# TS-4900_Headers.net
KiCad netlist of a schematic drawn in Altium Designer
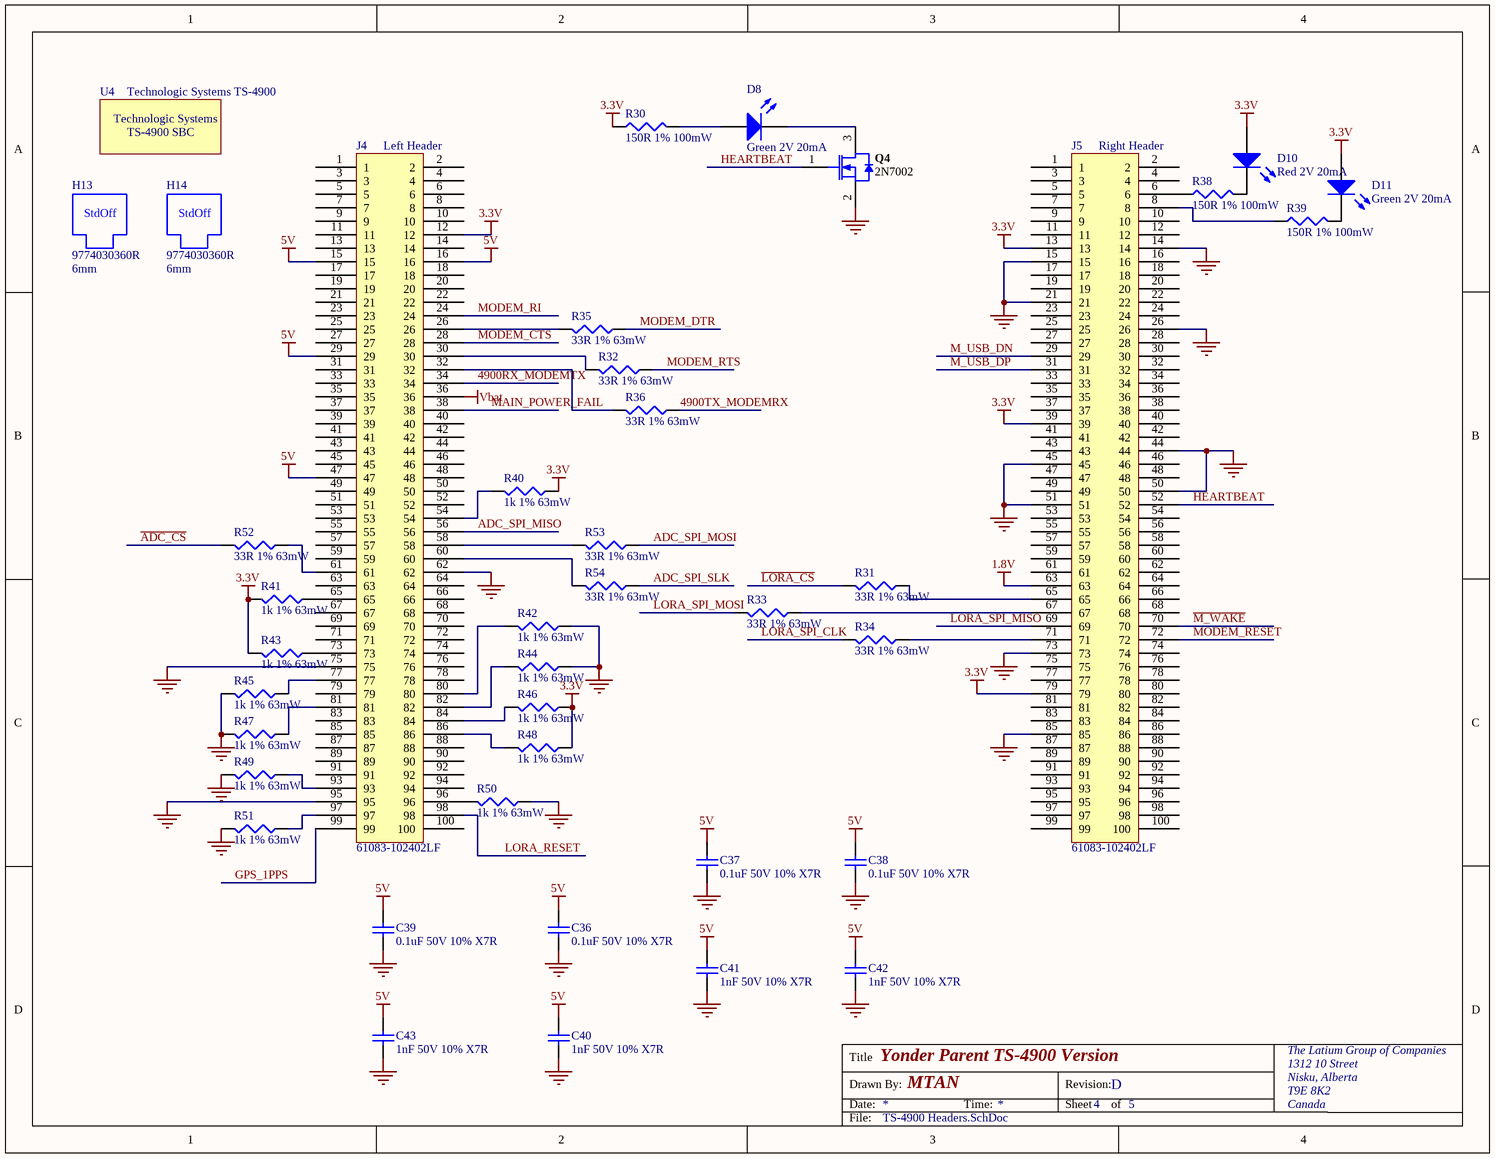
[diagram p0: TS-4900 Headers.SchDoc]

(export (version "E")
  (design (tool "Eeschema 10.0.6"))
  (components
    (comp (ref "C36")
      (value "0.1uF 50V 10% X7R")
      (footprint "CAPC1005L")
      (description "Capacitor")
      (libsource (lib "Miscellaneous Devices") (part "Cap"))
    )
    (comp (ref "C37")
      (value "0.1uF 50V 10% X7R")
      (footprint "CAPC1005L")
      (description "Capacitor")
      (libsource (lib "Miscellaneous Devices") (part "Cap"))
    )
    (comp (ref "C38")
      (value "0.1uF 50V 10% X7R")
      (footprint "CAPC1005L")
      (description "Capacitor")
      (libsource (lib "Miscellaneous Devices") (part "Cap"))
    )
    (comp (ref "C39")
      (value "0.1uF 50V 10% X7R")
      (footprint "CAPC1005L")
      (description "Capacitor")
      (libsource (lib "Miscellaneous Devices") (part "Cap"))
    )
    (comp (ref "C40")
      (value "1nF 50V 10% X7R")
      (footprint "CAPC1005L")
      (description "Capacitor")
      (libsource (lib "Miscellaneous Devices") (part "Cap"))
    )
    (comp (ref "C41")
      (value "1nF 50V 10% X7R")
      (footprint "CAPC1005L")
      (description "Capacitor")
      (libsource (lib "Miscellaneous Devices") (part "Cap"))
    )
    (comp (ref "C42")
      (value "1nF 50V 10% X7R")
      (footprint "CAPC1005L")
      (description "Capacitor")
      (libsource (lib "Miscellaneous Devices") (part "Cap"))
    )
    (comp (ref "C43")
      (value "1nF 50V 10% X7R")
      (footprint "CAPC1005L")
      (description "Capacitor")
      (libsource (lib "Miscellaneous Devices") (part "Cap"))
    )
    (comp (ref "D8")
      (value "Green 2V 20mA")
      (footprint "CD1608-0603")
      (description "LED GREEN CLEAR 0603 SMD")
      (fields
        (field (name "MANUFACTURER") "Wurth Electronics Inc")
        (field (name "MANUFACTURER PART NUMBER") "150060VS75000")
      )
      (libsource (lib "Miscellaneous Devices") (part "LED2"))
    )
    (comp (ref "D10")
      (value "Red 2V 20mA")
      (footprint "CD1608-0603")
      (description "LED RED CLEAR 0603 SMD")
      (fields
        (field (name "MANUFACTURER") "Wurth Electronics Inc")
        (field (name "MANUFACTURER PART NUMBER") "150060RS75000")
      )
      (libsource (lib "Miscellaneous Devices") (part "LED2"))
    )
    (comp (ref "D11")
      (value "Green 2V 20mA")
      (footprint "CD1608-0603")
      (description "LED GREEN CLEAR 0603 SMD")
      (fields
        (field (name "MANUFACTURER") "Wurth Electronics Inc")
        (field (name "MANUFACTURER PART NUMBER") "150060VS75000")
      )
      (libsource (lib "Miscellaneous Devices") (part "LED2"))
    )
    (comp (ref "H13")
      (value "9774030360R")
      (footprint "Wurth 9774060360R")
      (description "ROUND STANDOFF M3X0.5 STEEL 6MM")
      (fields
        (field (name "MANUFACTURER") "Wurth Electronics Inc")
        (field (name "MANUFACTURER PART NUMBER") "9774060360R")
        (field (name "HEIGHT") "6mm")
      )
      (libsource (lib "Latium Component Library") (part "SMD M3 Spacer"))
    )
    (comp (ref "H14")
      (value "9774030360R")
      (footprint "Wurth 9774060360R")
      (description "ROUND STANDOFF M3X0.5 STEEL 6MM")
      (fields
        (field (name "MANUFACTURER") "Wurth Electronics Inc")
        (field (name "MANUFACTURER PART NUMBER") "9774060360R")
        (field (name "HEIGHT") "6mm")
      )
      (libsource (lib "Latium Component Library") (part "SMD M3 Spacer"))
    )
    (comp (ref "J4")
      (value "61083-102402LF")
      (footprint "TS 100 Pin Header")
      (description "CONN PLUG 100POS SMD GOLD")
      (fields (field (name "MANUFACTURER") "Amphenol ICC (FCI)") (field (name "NOTE") "Left Header"))
      (libsource (lib "Latium Component Library") (part "Header 50 x 2"))
    )
    (comp (ref "J5")
      (value "61083-102402LF")
      (footprint "TS 100 Pin Header")
      (description "CONN PLUG 100POS SMD GOLD")
      (fields (field (name "MANUFACTURER") "Amphenol ICC (FCI)") (field (name "NOTE") "Right Header"))
      (libsource (lib "Latium Component Library") (part "Header 50 x 2"))
    )
    (comp (ref "Q4")
      (value "2N7002")
      (footprint "INF-PG-SOT23_L")
      (description "MOSFET N-CH 60V 115MA SOT-23")
      (fields (field (name "MANUFACTURER") "ON Semiconductor"))
      (libsource (lib "Infineon Power MOSFET") (part "2N7002"))
    )
    (comp (ref "R30")
      (value "150R 1% 100mW")
      (footprint "RESC1608L")
      (description "Resistor")
      (libsource (lib "Miscellaneous Devices") (part "Res3"))
    )
    (comp (ref "R31")
      (value "33R 1% 63mW")
      (footprint "RESC1005L")
      (description "Resistor")
      (libsource (lib "Miscellaneous Devices") (part "Res3"))
    )
    (comp (ref "R32")
      (value "33R 1% 63mW")
      (footprint "RESC1005L")
      (description "Resistor")
      (libsource (lib "Miscellaneous Devices") (part "Res3"))
    )
    (comp (ref "R33")
      (value "33R 1% 63mW")
      (footprint "RESC1005L")
      (description "Resistor")
      (libsource (lib "Miscellaneous Devices") (part "Res3"))
    )
    (comp (ref "R34")
      (value "33R 1% 63mW")
      (footprint "RESC1005L")
      (description "Resistor")
      (libsource (lib "Miscellaneous Devices") (part "Res3"))
    )
    (comp (ref "R35")
      (value "33R 1% 63mW")
      (footprint "RESC1005L")
      (description "Resistor")
      (libsource (lib "Miscellaneous Devices") (part "Res3"))
    )
    (comp (ref "R36")
      (value "33R 1% 63mW")
      (footprint "RESC1005L")
      (description "Resistor")
      (libsource (lib "Miscellaneous Devices") (part "Res3"))
    )
    (comp (ref "R38")
      (value "150R 1% 100mW")
      (footprint "RESC1608L")
      (description "Resistor")
      (libsource (lib "Miscellaneous Devices") (part "Res3"))
    )
    (comp (ref "R39")
      (value "150R 1% 100mW")
      (footprint "RESC1608L")
      (description "Resistor")
      (libsource (lib "Miscellaneous Devices") (part "Res3"))
    )
    (comp (ref "R40")
      (value "1k 1% 63mW")
      (footprint "RESC1005L")
      (description "Resistor")
      (libsource (lib "Miscellaneous Devices") (part "Res3"))
    )
    (comp (ref "R41")
      (value "1k 1% 63mW")
      (footprint "RESC1005L")
      (description "Resistor")
      (libsource (lib "Miscellaneous Devices") (part "Res3"))
    )
    (comp (ref "R42")
      (value "1k 1% 63mW")
      (footprint "RESC1005L")
      (description "Resistor")
      (libsource (lib "Miscellaneous Devices") (part "Res3"))
    )
    (comp (ref "R43")
      (value "1k 1% 63mW")
      (footprint "RESC1005L")
      (description "Resistor")
      (libsource (lib "Miscellaneous Devices") (part "Res3"))
    )
    (comp (ref "R44")
      (value "1k 1% 63mW")
      (footprint "RESC1005L")
      (description "Resistor")
      (libsource (lib "Miscellaneous Devices") (part "Res3"))
    )
    (comp (ref "R45")
      (value "1k 1% 63mW")
      (footprint "RESC1005L")
      (description "Resistor")
      (libsource (lib "Miscellaneous Devices") (part "Res3"))
    )
    (comp (ref "R46")
      (value "1k 1% 63mW")
      (footprint "RESC1005L")
      (description "Resistor")
      (libsource (lib "Miscellaneous Devices") (part "Res3"))
    )
    (comp (ref "R47")
      (value "1k 1% 63mW")
      (footprint "RESC1005L")
      (description "Resistor")
      (libsource (lib "Miscellaneous Devices") (part "Res3"))
    )
    (comp (ref "R48")
      (value "1k 1% 63mW")
      (footprint "RESC1005L")
      (description "Resistor")
      (libsource (lib "Miscellaneous Devices") (part "Res3"))
    )
    (comp (ref "R49")
      (value "1k 1% 63mW")
      (footprint "RESC1005L")
      (description "Resistor")
      (libsource (lib "Miscellaneous Devices") (part "Res3"))
    )
    (comp (ref "R50")
      (value "1k 1% 63mW")
      (footprint "RESC1005L")
      (description "Resistor")
      (libsource (lib "Miscellaneous Devices") (part "Res3"))
    )
    (comp (ref "R51")
      (value "1k 1% 63mW")
      (footprint "RESC1005L")
      (description "Resistor")
      (libsource (lib "Miscellaneous Devices") (part "Res3"))
    )
    (comp (ref "R52")
      (value "33R 1% 63mW")
      (footprint "RESC1005L")
      (description "Resistor")
      (libsource (lib "Miscellaneous Devices") (part "Res3"))
    )
    (comp (ref "R53")
      (value "33R 1% 63mW")
      (footprint "RESC1005L")
      (description "Resistor")
      (libsource (lib "Miscellaneous Devices") (part "Res3"))
    )
    (comp (ref "R54")
      (value "33R 1% 63mW")
      (footprint "RESC1005L")
      (description "Resistor")
      (libsource (lib "Miscellaneous Devices") (part "Res3"))
    )
    (comp (ref "U4")
      (value "Technologic Systems TS-4900")
      (footprint "TS-4900")
      (libsource (lib "Latium Component Library") (part "TS-4900"))
    )
  )
  (nets
    (net (code "1") (name "/4900RX_MODEMTX") (class "Default")
      (node (ref "J4") (pin "34") (pinfunction "34_34") (pintype "passive"))
    )
    (net (code "2") (name "/4900TX_MODEMRX") (class "Default")
      (node (ref "R36") (pin "1") (pinfunction "1_1") (pintype "passive"))
    )
    (net (code "3") (name "/ADC_SPI_MISO") (class "Default")
      (node (ref "J4") (pin "56") (pinfunction "56_56") (pintype "passive"))
    )
    (net (code "4") (name "/ADC_SPI_MOSI") (class "Default")
      (node (ref "R53") (pin "1") (pinfunction "1_1") (pintype "passive"))
    )
    (net (code "5") (name "/ADC_SPI_SLK") (class "Default")
      (node (ref "R54") (pin "1") (pinfunction "1_1") (pintype "passive"))
    )
    (net (code "6") (name "/GPS_1PPS") (class "Default")
      (node (ref "J4") (pin "99") (pinfunction "99_99") (pintype "passive"))
    )
    (net (code "7") (name "/HEARTBEAT") (class "Default")
      (node (ref "J5") (pin "52") (pinfunction "52_52") (pintype "passive"))
      (node (ref "Q4") (pin "1") (pinfunction "GATE_1") (pintype "passive"))
    )
    (net (code "8") (name "/LORA_RESET") (class "Default")
      (node (ref "J4") (pin "98") (pinfunction "98_98") (pintype "passive"))
    )
    (net (code "9") (name "/LORA_SPI_CLK") (class "Default")
      (node (ref "R34") (pin "2") (pinfunction "2_2") (pintype "passive"))
    )
    (net (code "10") (name "/LORA_SPI_MISO") (class "Default")
      (node (ref "J5") (pin "69") (pinfunction "69_69") (pintype "passive"))
    )
    (net (code "11") (name "/LORA_SPI_MOSI") (class "Default")
      (node (ref "R33") (pin "2") (pinfunction "2_2") (pintype "passive"))
    )
    (net (code "12") (name "/MAIN_POWER_FAIL") (class "Default")
      (node (ref "J4") (pin "38") (pinfunction "38_38") (pintype "passive"))
    )
    (net (code "13") (name "/MODEM_CTS") (class "Default")
      (node (ref "J4") (pin "28") (pinfunction "28_28") (pintype "passive"))
    )
    (net (code "14") (name "/MODEM_DTR") (class "Default")
      (node (ref "R35") (pin "1") (pinfunction "1_1") (pintype "passive"))
    )
    (net (code "15") (name "/MODEM_RESET") (class "Default")
      (node (ref "J5") (pin "72") (pinfunction "72_72") (pintype "passive"))
    )
    (net (code "16") (name "/MODEM_RI") (class "Default")
      (node (ref "J4") (pin "24") (pinfunction "24_24") (pintype "passive"))
    )
    (net (code "17") (name "/MODEM_RTS") (class "Default")
      (node (ref "R32") (pin "1") (pinfunction "1_1") (pintype "passive"))
    )
    (net (code "18") (name "/M_USB_DN") (class "Default")
      (node (ref "J5") (pin "29") (pinfunction "29_29") (pintype "passive"))
    )
    (net (code "19") (name "/M_USB_DP") (class "Default")
      (node (ref "J5") (pin "31") (pinfunction "31_31") (pintype "passive"))
    )
    (net (code "20") (name "/~{ADC_CS}") (class "Default")
      (node (ref "R52") (pin "2") (pinfunction "2_2") (pintype "passive"))
    )
    (net (code "21") (name "/~{LORA_CS}") (class "Default")
      (node (ref "R31") (pin "2") (pinfunction "2_2") (pintype "passive"))
    )
    (net (code "22") (name "/~{M_WAKE}") (class "Default")
      (node (ref "J5") (pin "70") (pinfunction "70_70") (pintype "passive"))
    )
    (net (code "23") (name "1.8V") (class "Default")
      (node (ref "J5") (pin "63") (pinfunction "63_63") (pintype "passive"))
    )
    (net (code "24") (name "3.3V") (class "Default")
      (node (ref "D10") (pin "1") (pinfunction "A_1") (pintype "passive"))
      (node (ref "D11") (pin "1") (pinfunction "A_1") (pintype "passive"))
      (node (ref "J4") (pin "12") (pinfunction "12_12") (pintype "passive"))
      (node (ref "J5") (pin "13") (pinfunction "13_13") (pintype "passive"))
      (node (ref "J5") (pin "39") (pinfunction "39_39") (pintype "passive"))
      (node (ref "J5") (pin "79") (pinfunction "79_79") (pintype "passive"))
      (node (ref "R30") (pin "1") (pinfunction "1_1") (pintype "passive"))
      (node (ref "R40") (pin "1") (pinfunction "1_1") (pintype "passive"))
      (node (ref "R41") (pin "2") (pinfunction "2_2") (pintype "passive"))
      (node (ref "R43") (pin "2") (pinfunction "2_2") (pintype "passive"))
      (node (ref "R46") (pin "1") (pinfunction "1_1") (pintype "passive"))
      (node (ref "R48") (pin "1") (pinfunction "1_1") (pintype "passive"))
    )
    (net (code "25") (name "5V") (class "Default")
      (node (ref "C36") (pin "1") (pinfunction "1_1") (pintype "passive"))
      (node (ref "C37") (pin "1") (pinfunction "1_1") (pintype "passive"))
      (node (ref "C38") (pin "1") (pinfunction "1_1") (pintype "passive"))
      (node (ref "C39") (pin "1") (pinfunction "1_1") (pintype "passive"))
      (node (ref "C40") (pin "1") (pinfunction "1_1") (pintype "passive"))
      (node (ref "C41") (pin "1") (pinfunction "1_1") (pintype "passive"))
      (node (ref "C42") (pin "1") (pinfunction "1_1") (pintype "passive"))
      (node (ref "C43") (pin "1") (pinfunction "1_1") (pintype "passive"))
      (node (ref "J4") (pin "15") (pinfunction "15_15") (pintype "passive"))
      (node (ref "J4") (pin "16") (pinfunction "16_16") (pintype "passive"))
      (node (ref "J4") (pin "29") (pinfunction "29_29") (pintype "passive"))
      (node (ref "J4") (pin "47") (pinfunction "47_47") (pintype "passive"))
    )
    (net (code "26") (name "GND") (class "Default")
      (node (ref "C36") (pin "2") (pinfunction "2_2") (pintype "passive"))
      (node (ref "C37") (pin "2") (pinfunction "2_2") (pintype "passive"))
      (node (ref "C38") (pin "2") (pinfunction "2_2") (pintype "passive"))
      (node (ref "C39") (pin "2") (pinfunction "2_2") (pintype "passive"))
      (node (ref "C40") (pin "2") (pinfunction "2_2") (pintype "passive"))
      (node (ref "C41") (pin "2") (pinfunction "2_2") (pintype "passive"))
      (node (ref "C42") (pin "2") (pinfunction "2_2") (pintype "passive"))
      (node (ref "C43") (pin "2") (pinfunction "2_2") (pintype "passive"))
      (node (ref "J4") (pin "62") (pinfunction "62_62") (pintype "passive"))
      (node (ref "J4") (pin "75") (pinfunction "75_75") (pintype "passive"))
      (node (ref "J4") (pin "95") (pinfunction "95_95") (pintype "passive"))
      (node (ref "J5") (pin "14") (pinfunction "14_14") (pintype "passive"))
      (node (ref "J5") (pin "15") (pinfunction "15_15") (pintype "passive"))
      (node (ref "J5") (pin "21") (pinfunction "21_21") (pintype "passive"))
      (node (ref "J5") (pin "26") (pinfunction "26_26") (pintype "passive"))
      (node (ref "J5") (pin "44") (pinfunction "44_44") (pintype "passive"))
      (node (ref "J5") (pin "45") (pinfunction "45_45") (pintype "passive"))
      (node (ref "J5") (pin "50") (pinfunction "50_50") (pintype "passive"))
      (node (ref "J5") (pin "51") (pinfunction "51_51") (pintype "passive"))
      (node (ref "J5") (pin "73") (pinfunction "73_73") (pintype "passive"))
      (node (ref "J5") (pin "85") (pinfunction "85_85") (pintype "passive"))
      (node (ref "Q4") (pin "2") (pinfunction "SOURCE_2") (pintype "passive"))
      (node (ref "R42") (pin "1") (pinfunction "1_1") (pintype "passive"))
      (node (ref "R44") (pin "1") (pinfunction "1_1") (pintype "passive"))
      (node (ref "R45") (pin "2") (pinfunction "2_2") (pintype "passive"))
      (node (ref "R47") (pin "2") (pinfunction "2_2") (pintype "passive"))
      (node (ref "R49") (pin "2") (pinfunction "2_2") (pintype "passive"))
      (node (ref "R50") (pin "1") (pinfunction "1_1") (pintype "passive"))
      (node (ref "R51") (pin "2") (pinfunction "2_2") (pintype "passive"))
    )
    (net (code "27") (name "Net-(D8-A)") (class "Default")
      (node (ref "D8") (pin "1") (pinfunction "A_1") (pintype "passive"))
      (node (ref "R30") (pin "2") (pinfunction "2_2") (pintype "passive"))
    )
    (net (code "28") (name "Net-(D8-K)") (class "Default")
      (node (ref "D8") (pin "2") (pinfunction "K_2") (pintype "passive"))
      (node (ref "Q4") (pin "3") (pinfunction "DRAIN_3") (pintype "passive"))
    )
    (net (code "29") (name "Net-(D10-K)") (class "Default")
      (node (ref "D10") (pin "2") (pinfunction "K_2") (pintype "passive"))
      (node (ref "R38") (pin "2") (pinfunction "2_2") (pintype "passive"))
    )
    (net (code "30") (name "Net-(D11-K)") (class "Default")
      (node (ref "D11") (pin "2") (pinfunction "K_2") (pintype "passive"))
      (node (ref "R39") (pin "2") (pinfunction "2_2") (pintype "passive"))
    )
    (net (code "31") (name "Net-(J4-Pad26)") (class "Default")
      (node (ref "J4") (pin "26") (pinfunction "26_26") (pintype "passive"))
      (node (ref "R35") (pin "2") (pinfunction "2_2") (pintype "passive"))
    )
    (net (code "32") (name "Net-(J4-Pad30)") (class "Default")
      (node (ref "J4") (pin "30") (pinfunction "30_30") (pintype "passive"))
      (node (ref "R32") (pin "2") (pinfunction "2_2") (pintype "passive"))
    )
    (net (code "33") (name "Net-(J4-Pad32)") (class "Default")
      (node (ref "J4") (pin "32") (pinfunction "32_32") (pintype "passive"))
      (node (ref "R36") (pin "2") (pinfunction "2_2") (pintype "passive"))
    )
    (net (code "34") (name "Net-(J4-Pad54)") (class "Default")
      (node (ref "J4") (pin "54") (pinfunction "54_54") (pintype "passive"))
      (node (ref "R40") (pin "2") (pinfunction "2_2") (pintype "passive"))
    )
    (net (code "35") (name "Net-(J4-Pad58)") (class "Default")
      (node (ref "J4") (pin "58") (pinfunction "58_58") (pintype "passive"))
      (node (ref "R53") (pin "2") (pinfunction "2_2") (pintype "passive"))
    )
    (net (code "36") (name "Net-(J4-Pad60)") (class "Default")
      (node (ref "J4") (pin "60") (pinfunction "60_60") (pintype "passive"))
      (node (ref "R54") (pin "2") (pinfunction "2_2") (pintype "passive"))
    )
    (net (code "37") (name "Net-(J4-Pad61)") (class "Default")
      (node (ref "J4") (pin "61") (pinfunction "61_61") (pintype "passive"))
      (node (ref "R52") (pin "1") (pinfunction "1_1") (pintype "passive"))
    )
    (net (code "38") (name "Net-(J4-Pad65)") (class "Default")
      (node (ref "J4") (pin "65") (pinfunction "65_65") (pintype "passive"))
      (node (ref "R41") (pin "1") (pinfunction "1_1") (pintype "passive"))
    )
    (net (code "39") (name "Net-(J4-Pad73)") (class "Default")
      (node (ref "J4") (pin "73") (pinfunction "73_73") (pintype "passive"))
      (node (ref "R43") (pin "1") (pinfunction "1_1") (pintype "passive"))
    )
    (net (code "40") (name "Net-(J4-Pad77)") (class "Default")
      (node (ref "J4") (pin "77") (pinfunction "77_77") (pintype "passive"))
      (node (ref "R45") (pin "1") (pinfunction "1_1") (pintype "passive"))
    )
    (net (code "41") (name "Net-(J4-Pad80)") (class "Default")
      (node (ref "J4") (pin "80") (pinfunction "80_80") (pintype "passive"))
      (node (ref "R42") (pin "2") (pinfunction "2_2") (pintype "passive"))
    )
    (net (code "42") (name "Net-(J4-Pad81)") (class "Default")
      (node (ref "J4") (pin "81") (pinfunction "81_81") (pintype "passive"))
      (node (ref "R47") (pin "1") (pinfunction "1_1") (pintype "passive"))
    )
    (net (code "43") (name "Net-(J4-Pad82)") (class "Default")
      (node (ref "J4") (pin "82") (pinfunction "82_82") (pintype "passive"))
      (node (ref "R44") (pin "2") (pinfunction "2_2") (pintype "passive"))
    )
    (net (code "44") (name "Net-(J4-Pad84)") (class "Default")
      (node (ref "J4") (pin "84") (pinfunction "84_84") (pintype "passive"))
      (node (ref "R46") (pin "2") (pinfunction "2_2") (pintype "passive"))
    )
    (net (code "45") (name "Net-(J4-Pad86)") (class "Default")
      (node (ref "J4") (pin "86") (pinfunction "86_86") (pintype "passive"))
      (node (ref "R48") (pin "2") (pinfunction "2_2") (pintype "passive"))
    )
    (net (code "46") (name "Net-(J4-Pad93)") (class "Default")
      (node (ref "J4") (pin "93") (pinfunction "93_93") (pintype "passive"))
      (node (ref "R49") (pin "1") (pinfunction "1_1") (pintype "passive"))
    )
    (net (code "47") (name "Net-(J4-Pad96)") (class "Default")
      (node (ref "J4") (pin "96") (pinfunction "96_96") (pintype "passive"))
      (node (ref "R50") (pin "2") (pinfunction "2_2") (pintype "passive"))
    )
    (net (code "48") (name "Net-(J4-Pad97)") (class "Default")
      (node (ref "J4") (pin "97") (pinfunction "97_97") (pintype "passive"))
      (node (ref "R51") (pin "1") (pinfunction "1_1") (pintype "passive"))
    )
    (net (code "49") (name "Net-(J5-Pad6)") (class "Default")
      (node (ref "J5") (pin "6") (pinfunction "6_6") (pintype "passive"))
      (node (ref "R38") (pin "1") (pinfunction "1_1") (pintype "passive"))
    )
    (net (code "50") (name "Net-(J5-Pad8)") (class "Default")
      (node (ref "J5") (pin "8") (pinfunction "8_8") (pintype "passive"))
      (node (ref "R39") (pin "1") (pinfunction "1_1") (pintype "passive"))
    )
    (net (code "51") (name "Net-(J5-Pad65)") (class "Default")
      (node (ref "J5") (pin "65") (pinfunction "65_65") (pintype "passive"))
      (node (ref "R31") (pin "1") (pinfunction "1_1") (pintype "passive"))
    )
    (net (code "52") (name "Net-(J5-Pad67)") (class "Default")
      (node (ref "J5") (pin "67") (pinfunction "67_67") (pintype "passive"))
      (node (ref "R33") (pin "1") (pinfunction "1_1") (pintype "passive"))
    )
    (net (code "53") (name "Net-(J5-Pad71)") (class "Default")
      (node (ref "J5") (pin "71") (pinfunction "71_71") (pintype "passive"))
      (node (ref "R34") (pin "1") (pinfunction "1_1") (pintype "passive"))
    )
    (net (code "54") (name "Vbat") (class "Default")
      (node (ref "J4") (pin "36") (pinfunction "36_36") (pintype "passive"))
    )
    (net (code "55") (name "unconnected-(J4-Pad1)") (class "Default")
      (node (ref "J4") (pin "1") (pinfunction "1_1") (pintype "passive"))
    )
    (net (code "56") (name "unconnected-(J4-Pad2)") (class "Default")
      (node (ref "J4") (pin "2") (pinfunction "2_2") (pintype "passive"))
    )
    (net (code "57") (name "unconnected-(J4-Pad3)") (class "Default")
      (node (ref "J4") (pin "3") (pinfunction "3_3") (pintype "passive"))
    )
    (net (code "58") (name "unconnected-(J4-Pad4)") (class "Default")
      (node (ref "J4") (pin "4") (pinfunction "4_4") (pintype "passive"))
    )
    (net (code "59") (name "unconnected-(J4-Pad5)") (class "Default")
      (node (ref "J4") (pin "5") (pinfunction "5_5") (pintype "passive"))
    )
    (net (code "60") (name "unconnected-(J4-Pad6)") (class "Default")
      (node (ref "J4") (pin "6") (pinfunction "6_6") (pintype "passive"))
    )
    (net (code "61") (name "unconnected-(J4-Pad7)") (class "Default")
      (node (ref "J4") (pin "7") (pinfunction "7_7") (pintype "passive"))
    )
    (net (code "62") (name "unconnected-(J4-Pad8)") (class "Default")
      (node (ref "J4") (pin "8") (pinfunction "8_8") (pintype "passive"))
    )
    (net (code "63") (name "unconnected-(J4-Pad9)") (class "Default")
      (node (ref "J4") (pin "9") (pinfunction "9_9") (pintype "passive"))
    )
    (net (code "64") (name "unconnected-(J4-Pad10)") (class "Default")
      (node (ref "J4") (pin "10") (pinfunction "10_10") (pintype "passive"))
    )
    (net (code "65") (name "unconnected-(J4-Pad11)") (class "Default")
      (node (ref "J4") (pin "11") (pinfunction "11_11") (pintype "passive"))
    )
    (net (code "66") (name "unconnected-(J4-Pad13)") (class "Default")
      (node (ref "J4") (pin "13") (pinfunction "13_13") (pintype "passive"))
    )
    (net (code "67") (name "unconnected-(J4-Pad14)") (class "Default")
      (node (ref "J4") (pin "14") (pinfunction "14_14") (pintype "passive"))
    )
    (net (code "68") (name "unconnected-(J4-Pad17)") (class "Default")
      (node (ref "J4") (pin "17") (pinfunction "17_17") (pintype "passive"))
    )
    (net (code "69") (name "unconnected-(J4-Pad18)") (class "Default")
      (node (ref "J4") (pin "18") (pinfunction "18_18") (pintype "passive"))
    )
    (net (code "70") (name "unconnected-(J4-Pad19)") (class "Default")
      (node (ref "J4") (pin "19") (pinfunction "19_19") (pintype "passive"))
    )
    (net (code "71") (name "unconnected-(J4-Pad20)") (class "Default")
      (node (ref "J4") (pin "20") (pinfunction "20_20") (pintype "passive"))
    )
    (net (code "72") (name "unconnected-(J4-Pad21)") (class "Default")
      (node (ref "J4") (pin "21") (pinfunction "21_21") (pintype "passive"))
    )
    (net (code "73") (name "unconnected-(J4-Pad22)") (class "Default")
      (node (ref "J4") (pin "22") (pinfunction "22_22") (pintype "passive"))
    )
    (net (code "74") (name "unconnected-(J4-Pad23)") (class "Default")
      (node (ref "J4") (pin "23") (pinfunction "23_23") (pintype "passive"))
    )
    (net (code "75") (name "unconnected-(J4-Pad25)") (class "Default")
      (node (ref "J4") (pin "25") (pinfunction "25_25") (pintype "passive"))
    )
    (net (code "76") (name "unconnected-(J4-Pad27)") (class "Default")
      (node (ref "J4") (pin "27") (pinfunction "27_27") (pintype "passive"))
    )
    (net (code "77") (name "unconnected-(J4-Pad31)") (class "Default")
      (node (ref "J4") (pin "31") (pinfunction "31_31") (pintype "passive"))
    )
    (net (code "78") (name "unconnected-(J4-Pad33)") (class "Default")
      (node (ref "J4") (pin "33") (pinfunction "33_33") (pintype "passive"))
    )
    (net (code "79") (name "unconnected-(J4-Pad35)") (class "Default")
      (node (ref "J4") (pin "35") (pinfunction "35_35") (pintype "passive"))
    )
    (net (code "80") (name "unconnected-(J4-Pad37)") (class "Default")
      (node (ref "J4") (pin "37") (pinfunction "37_37") (pintype "passive"))
    )
    (net (code "81") (name "unconnected-(J4-Pad39)") (class "Default")
      (node (ref "J4") (pin "39") (pinfunction "39_39") (pintype "passive"))
    )
    (net (code "82") (name "unconnected-(J4-Pad40)") (class "Default")
      (node (ref "J4") (pin "40") (pinfunction "40_40") (pintype "passive"))
    )
    (net (code "83") (name "unconnected-(J4-Pad41)") (class "Default")
      (node (ref "J4") (pin "41") (pinfunction "41_41") (pintype "passive"))
    )
    (net (code "84") (name "unconnected-(J4-Pad42)") (class "Default")
      (node (ref "J4") (pin "42") (pinfunction "42_42") (pintype "passive"))
    )
    (net (code "85") (name "unconnected-(J4-Pad43)") (class "Default")
      (node (ref "J4") (pin "43") (pinfunction "43_43") (pintype "passive"))
    )
    (net (code "86") (name "unconnected-(J4-Pad44)") (class "Default")
      (node (ref "J4") (pin "44") (pinfunction "44_44") (pintype "passive"))
    )
    (net (code "87") (name "unconnected-(J4-Pad45)") (class "Default")
      (node (ref "J4") (pin "45") (pinfunction "45_45") (pintype "passive"))
    )
    (net (code "88") (name "unconnected-(J4-Pad46)") (class "Default")
      (node (ref "J4") (pin "46") (pinfunction "46_46") (pintype "passive"))
    )
    (net (code "89") (name "unconnected-(J4-Pad48)") (class "Default")
      (node (ref "J4") (pin "48") (pinfunction "48_48") (pintype "passive"))
    )
    (net (code "90") (name "unconnected-(J4-Pad49)") (class "Default")
      (node (ref "J4") (pin "49") (pinfunction "49_49") (pintype "passive"))
    )
    (net (code "91") (name "unconnected-(J4-Pad50)") (class "Default")
      (node (ref "J4") (pin "50") (pinfunction "50_50") (pintype "passive"))
    )
    (net (code "92") (name "unconnected-(J4-Pad51)") (class "Default")
      (node (ref "J4") (pin "51") (pinfunction "51_51") (pintype "passive"))
    )
    (net (code "93") (name "unconnected-(J4-Pad52)") (class "Default")
      (node (ref "J4") (pin "52") (pinfunction "52_52") (pintype "passive"))
    )
    (net (code "94") (name "unconnected-(J4-Pad53)") (class "Default")
      (node (ref "J4") (pin "53") (pinfunction "53_53") (pintype "passive"))
    )
    (net (code "95") (name "unconnected-(J4-Pad55)") (class "Default")
      (node (ref "J4") (pin "55") (pinfunction "55_55") (pintype "passive"))
    )
    (net (code "96") (name "unconnected-(J4-Pad57)") (class "Default")
      (node (ref "J4") (pin "57") (pinfunction "57_57") (pintype "passive"))
    )
    (net (code "97") (name "unconnected-(J4-Pad59)") (class "Default")
      (node (ref "J4") (pin "59") (pinfunction "59_59") (pintype "passive"))
    )
    (net (code "98") (name "unconnected-(J4-Pad63)") (class "Default")
      (node (ref "J4") (pin "63") (pinfunction "63_63") (pintype "passive"))
    )
    (net (code "99") (name "unconnected-(J4-Pad64)") (class "Default")
      (node (ref "J4") (pin "64") (pinfunction "64_64") (pintype "passive"))
    )
    (net (code "100") (name "unconnected-(J4-Pad66)") (class "Default")
      (node (ref "J4") (pin "66") (pinfunction "66_66") (pintype "passive"))
    )
    (net (code "101") (name "unconnected-(J4-Pad67)") (class "Default")
      (node (ref "J4") (pin "67") (pinfunction "67_67") (pintype "passive"))
    )
    (net (code "102") (name "unconnected-(J4-Pad68)") (class "Default")
      (node (ref "J4") (pin "68") (pinfunction "68_68") (pintype "passive"))
    )
    (net (code "103") (name "unconnected-(J4-Pad69)") (class "Default")
      (node (ref "J4") (pin "69") (pinfunction "69_69") (pintype "passive"))
    )
    (net (code "104") (name "unconnected-(J4-Pad70)") (class "Default")
      (node (ref "J4") (pin "70") (pinfunction "70_70") (pintype "passive"))
    )
    (net (code "105") (name "unconnected-(J4-Pad71)") (class "Default")
      (node (ref "J4") (pin "71") (pinfunction "71_71") (pintype "passive"))
    )
    (net (code "106") (name "unconnected-(J4-Pad72)") (class "Default")
      (node (ref "J4") (pin "72") (pinfunction "72_72") (pintype "passive"))
    )
    (net (code "107") (name "unconnected-(J4-Pad74)") (class "Default")
      (node (ref "J4") (pin "74") (pinfunction "74_74") (pintype "passive"))
    )
    (net (code "108") (name "unconnected-(J4-Pad76)") (class "Default")
      (node (ref "J4") (pin "76") (pinfunction "76_76") (pintype "passive"))
    )
    (net (code "109") (name "unconnected-(J4-Pad78)") (class "Default")
      (node (ref "J4") (pin "78") (pinfunction "78_78") (pintype "passive"))
    )
    (net (code "110") (name "unconnected-(J4-Pad79)") (class "Default")
      (node (ref "J4") (pin "79") (pinfunction "79_79") (pintype "passive"))
    )
    (net (code "111") (name "unconnected-(J4-Pad83)") (class "Default")
      (node (ref "J4") (pin "83") (pinfunction "83_83") (pintype "passive"))
    )
    (net (code "112") (name "unconnected-(J4-Pad85)") (class "Default")
      (node (ref "J4") (pin "85") (pinfunction "85_85") (pintype "passive"))
    )
    (net (code "113") (name "unconnected-(J4-Pad87)") (class "Default")
      (node (ref "J4") (pin "87") (pinfunction "87_87") (pintype "passive"))
    )
    (net (code "114") (name "unconnected-(J4-Pad88)") (class "Default")
      (node (ref "J4") (pin "88") (pinfunction "88_88") (pintype "passive"))
    )
    (net (code "115") (name "unconnected-(J4-Pad89)") (class "Default")
      (node (ref "J4") (pin "89") (pinfunction "89_89") (pintype "passive"))
    )
    (net (code "116") (name "unconnected-(J4-Pad90)") (class "Default")
      (node (ref "J4") (pin "90") (pinfunction "90_90") (pintype "passive"))
    )
    (net (code "117") (name "unconnected-(J4-Pad91)") (class "Default")
      (node (ref "J4") (pin "91") (pinfunction "91_91") (pintype "passive"))
    )
    (net (code "118") (name "unconnected-(J4-Pad92)") (class "Default")
      (node (ref "J4") (pin "92") (pinfunction "92_92") (pintype "passive"))
    )
    (net (code "119") (name "unconnected-(J4-Pad94)") (class "Default")
      (node (ref "J4") (pin "94") (pinfunction "94_94") (pintype "passive"))
    )
    (net (code "120") (name "unconnected-(J4-Pad100)") (class "Default")
      (node (ref "J4") (pin "100") (pinfunction "100_100") (pintype "passive"))
    )
    (net (code "121") (name "unconnected-(J5-Pad1)") (class "Default")
      (node (ref "J5") (pin "1") (pinfunction "1_1") (pintype "passive"))
    )
    (net (code "122") (name "unconnected-(J5-Pad2)") (class "Default")
      (node (ref "J5") (pin "2") (pinfunction "2_2") (pintype "passive"))
    )
    (net (code "123") (name "unconnected-(J5-Pad3)") (class "Default")
      (node (ref "J5") (pin "3") (pinfunction "3_3") (pintype "passive"))
    )
    (net (code "124") (name "unconnected-(J5-Pad4)") (class "Default")
      (node (ref "J5") (pin "4") (pinfunction "4_4") (pintype "passive"))
    )
    (net (code "125") (name "unconnected-(J5-Pad5)") (class "Default")
      (node (ref "J5") (pin "5") (pinfunction "5_5") (pintype "passive"))
    )
    (net (code "126") (name "unconnected-(J5-Pad7)") (class "Default")
      (node (ref "J5") (pin "7") (pinfunction "7_7") (pintype "passive"))
    )
    (net (code "127") (name "unconnected-(J5-Pad9)") (class "Default")
      (node (ref "J5") (pin "9") (pinfunction "9_9") (pintype "passive"))
    )
    (net (code "128") (name "unconnected-(J5-Pad10)") (class "Default")
      (node (ref "J5") (pin "10") (pinfunction "10_10") (pintype "passive"))
    )
    (net (code "129") (name "unconnected-(J5-Pad11)") (class "Default")
      (node (ref "J5") (pin "11") (pinfunction "11_11") (pintype "passive"))
    )
    (net (code "130") (name "unconnected-(J5-Pad12)") (class "Default")
      (node (ref "J5") (pin "12") (pinfunction "12_12") (pintype "passive"))
    )
    (net (code "131") (name "unconnected-(J5-Pad16)") (class "Default")
      (node (ref "J5") (pin "16") (pinfunction "16_16") (pintype "passive"))
    )
    (net (code "132") (name "unconnected-(J5-Pad17)") (class "Default")
      (node (ref "J5") (pin "17") (pinfunction "17_17") (pintype "passive"))
    )
    (net (code "133") (name "unconnected-(J5-Pad18)") (class "Default")
      (node (ref "J5") (pin "18") (pinfunction "18_18") (pintype "passive"))
    )
    (net (code "134") (name "unconnected-(J5-Pad19)") (class "Default")
      (node (ref "J5") (pin "19") (pinfunction "19_19") (pintype "passive"))
    )
    (net (code "135") (name "unconnected-(J5-Pad20)") (class "Default")
      (node (ref "J5") (pin "20") (pinfunction "20_20") (pintype "passive"))
    )
    (net (code "136") (name "unconnected-(J5-Pad22)") (class "Default")
      (node (ref "J5") (pin "22") (pinfunction "22_22") (pintype "passive"))
    )
    (net (code "137") (name "unconnected-(J5-Pad23)") (class "Default")
      (node (ref "J5") (pin "23") (pinfunction "23_23") (pintype "passive"))
    )
    (net (code "138") (name "unconnected-(J5-Pad24)") (class "Default")
      (node (ref "J5") (pin "24") (pinfunction "24_24") (pintype "passive"))
    )
    (net (code "139") (name "unconnected-(J5-Pad25)") (class "Default")
      (node (ref "J5") (pin "25") (pinfunction "25_25") (pintype "passive"))
    )
    (net (code "140") (name "unconnected-(J5-Pad27)") (class "Default")
      (node (ref "J5") (pin "27") (pinfunction "27_27") (pintype "passive"))
    )
    (net (code "141") (name "unconnected-(J5-Pad28)") (class "Default")
      (node (ref "J5") (pin "28") (pinfunction "28_28") (pintype "passive"))
    )
    (net (code "142") (name "unconnected-(J5-Pad30)") (class "Default")
      (node (ref "J5") (pin "30") (pinfunction "30_30") (pintype "passive"))
    )
    (net (code "143") (name "unconnected-(J5-Pad32)") (class "Default")
      (node (ref "J5") (pin "32") (pinfunction "32_32") (pintype "passive"))
    )
    (net (code "144") (name "unconnected-(J5-Pad33)") (class "Default")
      (node (ref "J5") (pin "33") (pinfunction "33_33") (pintype "passive"))
    )
    (net (code "145") (name "unconnected-(J5-Pad34)") (class "Default")
      (node (ref "J5") (pin "34") (pinfunction "34_34") (pintype "passive"))
    )
    (net (code "146") (name "unconnected-(J5-Pad35)") (class "Default")
      (node (ref "J5") (pin "35") (pinfunction "35_35") (pintype "passive"))
    )
    (net (code "147") (name "unconnected-(J5-Pad36)") (class "Default")
      (node (ref "J5") (pin "36") (pinfunction "36_36") (pintype "passive"))
    )
    (net (code "148") (name "unconnected-(J5-Pad37)") (class "Default")
      (node (ref "J5") (pin "37") (pinfunction "37_37") (pintype "passive"))
    )
    (net (code "149") (name "unconnected-(J5-Pad38)") (class "Default")
      (node (ref "J5") (pin "38") (pinfunction "38_38") (pintype "passive"))
    )
    (net (code "150") (name "unconnected-(J5-Pad40)") (class "Default")
      (node (ref "J5") (pin "40") (pinfunction "40_40") (pintype "passive"))
    )
    (net (code "151") (name "unconnected-(J5-Pad41)") (class "Default")
      (node (ref "J5") (pin "41") (pinfunction "41_41") (pintype "passive"))
    )
    (net (code "152") (name "unconnected-(J5-Pad42)") (class "Default")
      (node (ref "J5") (pin "42") (pinfunction "42_42") (pintype "passive"))
    )
    (net (code "153") (name "unconnected-(J5-Pad43)") (class "Default")
      (node (ref "J5") (pin "43") (pinfunction "43_43") (pintype "passive"))
    )
    (net (code "154") (name "unconnected-(J5-Pad46)") (class "Default")
      (node (ref "J5") (pin "46") (pinfunction "46_46") (pintype "passive"))
    )
    (net (code "155") (name "unconnected-(J5-Pad47)") (class "Default")
      (node (ref "J5") (pin "47") (pinfunction "47_47") (pintype "passive"))
    )
    (net (code "156") (name "unconnected-(J5-Pad48)") (class "Default")
      (node (ref "J5") (pin "48") (pinfunction "48_48") (pintype "passive"))
    )
    (net (code "157") (name "unconnected-(J5-Pad49)") (class "Default")
      (node (ref "J5") (pin "49") (pinfunction "49_49") (pintype "passive"))
    )
    (net (code "158") (name "unconnected-(J5-Pad53)") (class "Default")
      (node (ref "J5") (pin "53") (pinfunction "53_53") (pintype "passive"))
    )
    (net (code "159") (name "unconnected-(J5-Pad54)") (class "Default")
      (node (ref "J5") (pin "54") (pinfunction "54_54") (pintype "passive"))
    )
    (net (code "160") (name "unconnected-(J5-Pad55)") (class "Default")
      (node (ref "J5") (pin "55") (pinfunction "55_55") (pintype "passive"))
    )
    (net (code "161") (name "unconnected-(J5-Pad56)") (class "Default")
      (node (ref "J5") (pin "56") (pinfunction "56_56") (pintype "passive"))
    )
    (net (code "162") (name "unconnected-(J5-Pad57)") (class "Default")
      (node (ref "J5") (pin "57") (pinfunction "57_57") (pintype "passive"))
    )
    (net (code "163") (name "unconnected-(J5-Pad58)") (class "Default")
      (node (ref "J5") (pin "58") (pinfunction "58_58") (pintype "passive"))
    )
    (net (code "164") (name "unconnected-(J5-Pad59)") (class "Default")
      (node (ref "J5") (pin "59") (pinfunction "59_59") (pintype "passive"))
    )
    (net (code "165") (name "unconnected-(J5-Pad60)") (class "Default")
      (node (ref "J5") (pin "60") (pinfunction "60_60") (pintype "passive"))
    )
    (net (code "166") (name "unconnected-(J5-Pad61)") (class "Default")
      (node (ref "J5") (pin "61") (pinfunction "61_61") (pintype "passive"))
    )
    (net (code "167") (name "unconnected-(J5-Pad62)") (class "Default")
      (node (ref "J5") (pin "62") (pinfunction "62_62") (pintype "passive"))
    )
    (net (code "168") (name "unconnected-(J5-Pad64)") (class "Default")
      (node (ref "J5") (pin "64") (pinfunction "64_64") (pintype "passive"))
    )
    (net (code "169") (name "unconnected-(J5-Pad66)") (class "Default")
      (node (ref "J5") (pin "66") (pinfunction "66_66") (pintype "passive"))
    )
    (net (code "170") (name "unconnected-(J5-Pad68)") (class "Default")
      (node (ref "J5") (pin "68") (pinfunction "68_68") (pintype "passive"))
    )
    (net (code "171") (name "unconnected-(J5-Pad74)") (class "Default")
      (node (ref "J5") (pin "74") (pinfunction "74_74") (pintype "passive"))
    )
    (net (code "172") (name "unconnected-(J5-Pad75)") (class "Default")
      (node (ref "J5") (pin "75") (pinfunction "75_75") (pintype "passive"))
    )
    (net (code "173") (name "unconnected-(J5-Pad76)") (class "Default")
      (node (ref "J5") (pin "76") (pinfunction "76_76") (pintype "passive"))
    )
    (net (code "174") (name "unconnected-(J5-Pad77)") (class "Default")
      (node (ref "J5") (pin "77") (pinfunction "77_77") (pintype "passive"))
    )
    (net (code "175") (name "unconnected-(J5-Pad78)") (class "Default")
      (node (ref "J5") (pin "78") (pinfunction "78_78") (pintype "passive"))
    )
    (net (code "176") (name "unconnected-(J5-Pad80)") (class "Default")
      (node (ref "J5") (pin "80") (pinfunction "80_80") (pintype "passive"))
    )
    (net (code "177") (name "unconnected-(J5-Pad81)") (class "Default")
      (node (ref "J5") (pin "81") (pinfunction "81_81") (pintype "passive"))
    )
    (net (code "178") (name "unconnected-(J5-Pad82)") (class "Default")
      (node (ref "J5") (pin "82") (pinfunction "82_82") (pintype "passive"))
    )
    (net (code "179") (name "unconnected-(J5-Pad83)") (class "Default")
      (node (ref "J5") (pin "83") (pinfunction "83_83") (pintype "passive"))
    )
    (net (code "180") (name "unconnected-(J5-Pad84)") (class "Default")
      (node (ref "J5") (pin "84") (pinfunction "84_84") (pintype "passive"))
    )
    (net (code "181") (name "unconnected-(J5-Pad86)") (class "Default")
      (node (ref "J5") (pin "86") (pinfunction "86_86") (pintype "passive"))
    )
    (net (code "182") (name "unconnected-(J5-Pad87)") (class "Default")
      (node (ref "J5") (pin "87") (pinfunction "87_87") (pintype "passive"))
    )
    (net (code "183") (name "unconnected-(J5-Pad88)") (class "Default")
      (node (ref "J5") (pin "88") (pinfunction "88_88") (pintype "passive"))
    )
    (net (code "184") (name "unconnected-(J5-Pad89)") (class "Default")
      (node (ref "J5") (pin "89") (pinfunction "89_89") (pintype "passive"))
    )
    (net (code "185") (name "unconnected-(J5-Pad90)") (class "Default")
      (node (ref "J5") (pin "90") (pinfunction "90_90") (pintype "passive"))
    )
    (net (code "186") (name "unconnected-(J5-Pad91)") (class "Default")
      (node (ref "J5") (pin "91") (pinfunction "91_91") (pintype "passive"))
    )
    (net (code "187") (name "unconnected-(J5-Pad92)") (class "Default")
      (node (ref "J5") (pin "92") (pinfunction "92_92") (pintype "passive"))
    )
    (net (code "188") (name "unconnected-(J5-Pad93)") (class "Default")
      (node (ref "J5") (pin "93") (pinfunction "93_93") (pintype "passive"))
    )
    (net (code "189") (name "unconnected-(J5-Pad94)") (class "Default")
      (node (ref "J5") (pin "94") (pinfunction "94_94") (pintype "passive"))
    )
    (net (code "190") (name "unconnected-(J5-Pad95)") (class "Default")
      (node (ref "J5") (pin "95") (pinfunction "95_95") (pintype "passive"))
    )
    (net (code "191") (name "unconnected-(J5-Pad96)") (class "Default")
      (node (ref "J5") (pin "96") (pinfunction "96_96") (pintype "passive"))
    )
    (net (code "192") (name "unconnected-(J5-Pad97)") (class "Default")
      (node (ref "J5") (pin "97") (pinfunction "97_97") (pintype "passive"))
    )
    (net (code "193") (name "unconnected-(J5-Pad98)") (class "Default")
      (node (ref "J5") (pin "98") (pinfunction "98_98") (pintype "passive"))
    )
    (net (code "194") (name "unconnected-(J5-Pad99)") (class "Default")
      (node (ref "J5") (pin "99") (pinfunction "99_99") (pintype "passive"))
    )
    (net (code "195") (name "unconnected-(J5-Pad100)") (class "Default")
      (node (ref "J5") (pin "100") (pinfunction "100_100") (pintype "passive"))
    )
  )
)
